# controller.net
KiCad netlist of a schematic drawn in EAGLE
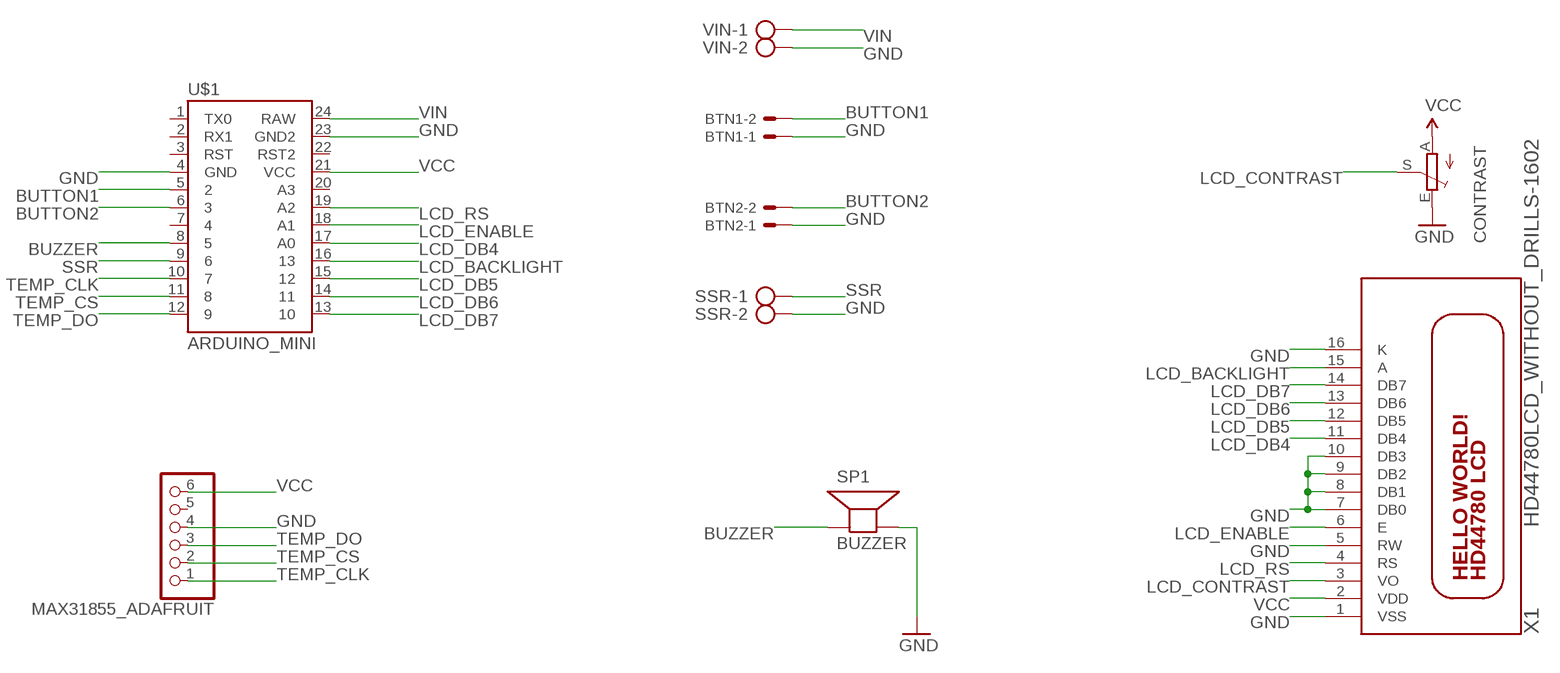
[diagram p0: schematic, sheet 1]

(export (version "E")
  (design (tool "Eeschema 10.0.6"))
  (components
    (comp (ref "BTN1")
      (value "22-27-2021-02")
      (footprint "eagle-import:6410-02")
      (libsource (lib "eagle-import") (part "22-?-0227-2021"))
    )
    (comp (ref "BTN2")
      (value "22-27-2021-02")
      (footprint "eagle-import:6410-02")
      (libsource (lib "eagle-import") (part "22-?-0227-2021"))
    )
    (comp (ref "CONTRAST")
      (value "TRIM_EU-B25U")
      (footprint "eagle-import:B25U")
      (libsource (lib "eagle-import") (part "TRIM_EU-B25U"))
    )
    (comp (ref "MAX31855_ADAFRUIT")
      (value "PINHD-1X6")
      (footprint "eagle-import:1X06")
      (libsource (lib "eagle-import") (part "PINHD-1X6"))
    )
    (comp (ref "SP1")
      (value "BUZZER")
      (footprint "eagle-import:PS12")
      (libsource (lib "eagle-import") (part "SPEAKER/PS12"))
    )
    (comp (ref "SSR")
      (value "AK500/2")
      (footprint "eagle-import:AK500_2")
      (libsource (lib "eagle-import") (part "AK500/2"))
    )
    (comp (ref "U$1")
      (value "ARDUINO_MINI")
      (footprint "eagle-import:ARDUINO_MINI")
      (libsource (lib "eagle-import") (part "ARDUINO_MINI"))
    )
    (comp (ref "VIN")
      (value "AK500/2")
      (footprint "eagle-import:AK500_2")
      (libsource (lib "eagle-import") (part "AK500/2"))
    )
    (comp (ref "X1")
      (value "HD44780LCD_WITHOUT_DRILLS-1602")
      (footprint "eagle-import:LCD1602")
      (libsource (lib "eagle-import") (part "HD44780LCD_WITHOUT_DRILLS-1602"))
    )
  )
  (nets
    (net (code "1") (name "/BUTTON1") (class "Default")
      (node (ref "BTN1") (pin "2") (pinfunction "S_2") (pintype "passive"))
      (node (ref "U$1") (pin "5") (pinfunction "2_5") (pintype "bidirectional"))
    )
    (net (code "2") (name "/BUTTON2") (class "Default")
      (node (ref "BTN2") (pin "2") (pinfunction "S_2") (pintype "passive"))
      (node (ref "U$1") (pin "6") (pinfunction "3_6") (pintype "bidirectional"))
    )
    (net (code "3") (name "/BUZZER") (class "Default")
      (node (ref "SP1") (pin "P$1") (pinfunction "+_P$1") (pintype "passive"))
      (node (ref "U$1") (pin "8") (pinfunction "5_8") (pintype "bidirectional"))
    )
    (net (code "4") (name "/LCD_BACKLIGHT") (class "Default")
      (node (ref "U$1") (pin "16") (pinfunction "13_16") (pintype "bidirectional"))
      (node (ref "X1") (pin "15") (pinfunction "A_15") (pintype "input"))
    )
    (net (code "5") (name "/LCD_CONTRAST") (class "Default")
      (node (ref "CONTRAST") (pin "S") (pinfunction "S_S") (pintype "passive"))
      (node (ref "X1") (pin "3") (pinfunction "VO_3") (pintype "input"))
    )
    (net (code "6") (name "/LCD_DB4") (class "Default")
      (node (ref "U$1") (pin "17") (pinfunction "A0_17") (pintype "bidirectional"))
      (node (ref "X1") (pin "11") (pinfunction "DB4_11") (pintype "bidirectional"))
    )
    (net (code "7") (name "/LCD_DB5") (class "Default")
      (node (ref "U$1") (pin "15") (pinfunction "12_15") (pintype "bidirectional"))
      (node (ref "X1") (pin "12") (pinfunction "DB5_12") (pintype "bidirectional"))
    )
    (net (code "8") (name "/LCD_DB6") (class "Default")
      (node (ref "U$1") (pin "14") (pinfunction "11_14") (pintype "bidirectional"))
      (node (ref "X1") (pin "13") (pinfunction "DB6_13") (pintype "bidirectional"))
    )
    (net (code "9") (name "/LCD_DB7") (class "Default")
      (node (ref "U$1") (pin "13") (pinfunction "10_13") (pintype "bidirectional"))
      (node (ref "X1") (pin "14") (pinfunction "DB7_14") (pintype "bidirectional"))
    )
    (net (code "10") (name "/LCD_ENABLE") (class "Default")
      (node (ref "U$1") (pin "18") (pinfunction "A1_18") (pintype "bidirectional"))
      (node (ref "X1") (pin "6") (pinfunction "E_6") (pintype "input"))
    )
    (net (code "11") (name "/LCD_RS") (class "Default")
      (node (ref "U$1") (pin "19") (pinfunction "A2_19") (pintype "bidirectional"))
      (node (ref "X1") (pin "4") (pinfunction "RS_4") (pintype "input"))
    )
    (net (code "12") (name "/SSR") (class "Default")
      (node (ref "SSR") (pin "1") (pinfunction "KL_1") (pintype "passive"))
      (node (ref "U$1") (pin "9") (pinfunction "6_9") (pintype "bidirectional"))
    )
    (net (code "13") (name "/TEMP_CLK") (class "Default")
      (node (ref "MAX31855_ADAFRUIT") (pin "1") (pinfunction "1_1") (pintype "passive"))
      (node (ref "U$1") (pin "10") (pinfunction "7_10") (pintype "bidirectional"))
    )
    (net (code "14") (name "/TEMP_CS") (class "Default")
      (node (ref "MAX31855_ADAFRUIT") (pin "2") (pinfunction "2_2") (pintype "passive"))
      (node (ref "U$1") (pin "11") (pinfunction "8_11") (pintype "bidirectional"))
    )
    (net (code "15") (name "/TEMP_DO") (class "Default")
      (node (ref "MAX31855_ADAFRUIT") (pin "3") (pinfunction "3_3") (pintype "passive"))
      (node (ref "U$1") (pin "12") (pinfunction "9_12") (pintype "bidirectional"))
    )
    (net (code "16") (name "/VIN") (class "Default")
      (node (ref "U$1") (pin "24") (pinfunction "RAW_24") (pintype "bidirectional"))
      (node (ref "VIN") (pin "1") (pinfunction "KL_1") (pintype "passive"))
    )
    (net (code "17") (name "GND") (class "Default")
      (node (ref "BTN1") (pin "1") (pinfunction "S_1") (pintype "passive"))
      (node (ref "BTN2") (pin "1") (pinfunction "S_1") (pintype "passive"))
      (node (ref "CONTRAST") (pin "E") (pinfunction "E_E") (pintype "passive"))
      (node (ref "MAX31855_ADAFRUIT") (pin "4") (pinfunction "4_4") (pintype "passive"))
      (node (ref "SP1") (pin "P$2") (pinfunction "-_P$2") (pintype "passive"))
      (node (ref "SSR") (pin "2") (pinfunction "KL_2") (pintype "passive"))
      (node (ref "U$1") (pin "23") (pinfunction "GND2_23") (pintype "bidirectional"))
      (node (ref "U$1") (pin "4") (pinfunction "GND_4") (pintype "bidirectional"))
      (node (ref "VIN") (pin "2") (pinfunction "KL_2") (pintype "passive"))
      (node (ref "X1") (pin "1") (pinfunction "VSS_1") (pintype "power_in"))
      (node (ref "X1") (pin "10") (pinfunction "DB3_10") (pintype "bidirectional"))
      (node (ref "X1") (pin "16") (pinfunction "K_16") (pintype "input"))
      (node (ref "X1") (pin "5") (pinfunction "RW_5") (pintype "input"))
      (node (ref "X1") (pin "7") (pinfunction "DB0_7") (pintype "bidirectional"))
      (node (ref "X1") (pin "8") (pinfunction "DB1_8") (pintype "bidirectional"))
      (node (ref "X1") (pin "9") (pinfunction "DB2_9") (pintype "bidirectional"))
    )
    (net (code "18") (name "VCC") (class "Default")
      (node (ref "CONTRAST") (pin "A") (pinfunction "A_A") (pintype "passive"))
      (node (ref "MAX31855_ADAFRUIT") (pin "6") (pinfunction "6_6") (pintype "passive"))
      (node (ref "U$1") (pin "21") (pinfunction "VCC_21") (pintype "bidirectional"))
      (node (ref "X1") (pin "2") (pinfunction "VDD_2") (pintype "power_in"))
    )
    (net (code "19") (name "unconnected-(MAX31855_ADAFRUIT-Pad5)") (class "Default")
      (node (ref "MAX31855_ADAFRUIT") (pin "5") (pinfunction "5_5") (pintype "passive"))
    )
    (net (code "20") (name "unconnected-(U$1-4-Pad7)") (class "Default")
      (node (ref "U$1") (pin "7") (pinfunction "4_7") (pintype "bidirectional"))
    )
    (net (code "21") (name "unconnected-(U$1-A3-Pad20)") (class "Default")
      (node (ref "U$1") (pin "20") (pinfunction "A3_20") (pintype "bidirectional"))
    )
    (net (code "22") (name "unconnected-(U$1-RST-Pad3)") (class "Default")
      (node (ref "U$1") (pin "3") (pinfunction "RST_3") (pintype "bidirectional"))
    )
    (net (code "23") (name "unconnected-(U$1-RST2-Pad22)") (class "Default")
      (node (ref "U$1") (pin "22") (pinfunction "RST2_22") (pintype "bidirectional"))
    )
    (net (code "24") (name "unconnected-(U$1-RX1-Pad2)") (class "Default")
      (node (ref "U$1") (pin "2") (pinfunction "RX1_2") (pintype "bidirectional"))
    )
    (net (code "25") (name "unconnected-(U$1-TX0-Pad1)") (class "Default")
      (node (ref "U$1") (pin "1") (pinfunction "TX0_1") (pintype "bidirectional"))
    )
  )
)
